# 1_Sheet_1_schdoc.net
KiCad netlist of a schematic drawn in Altium Designer
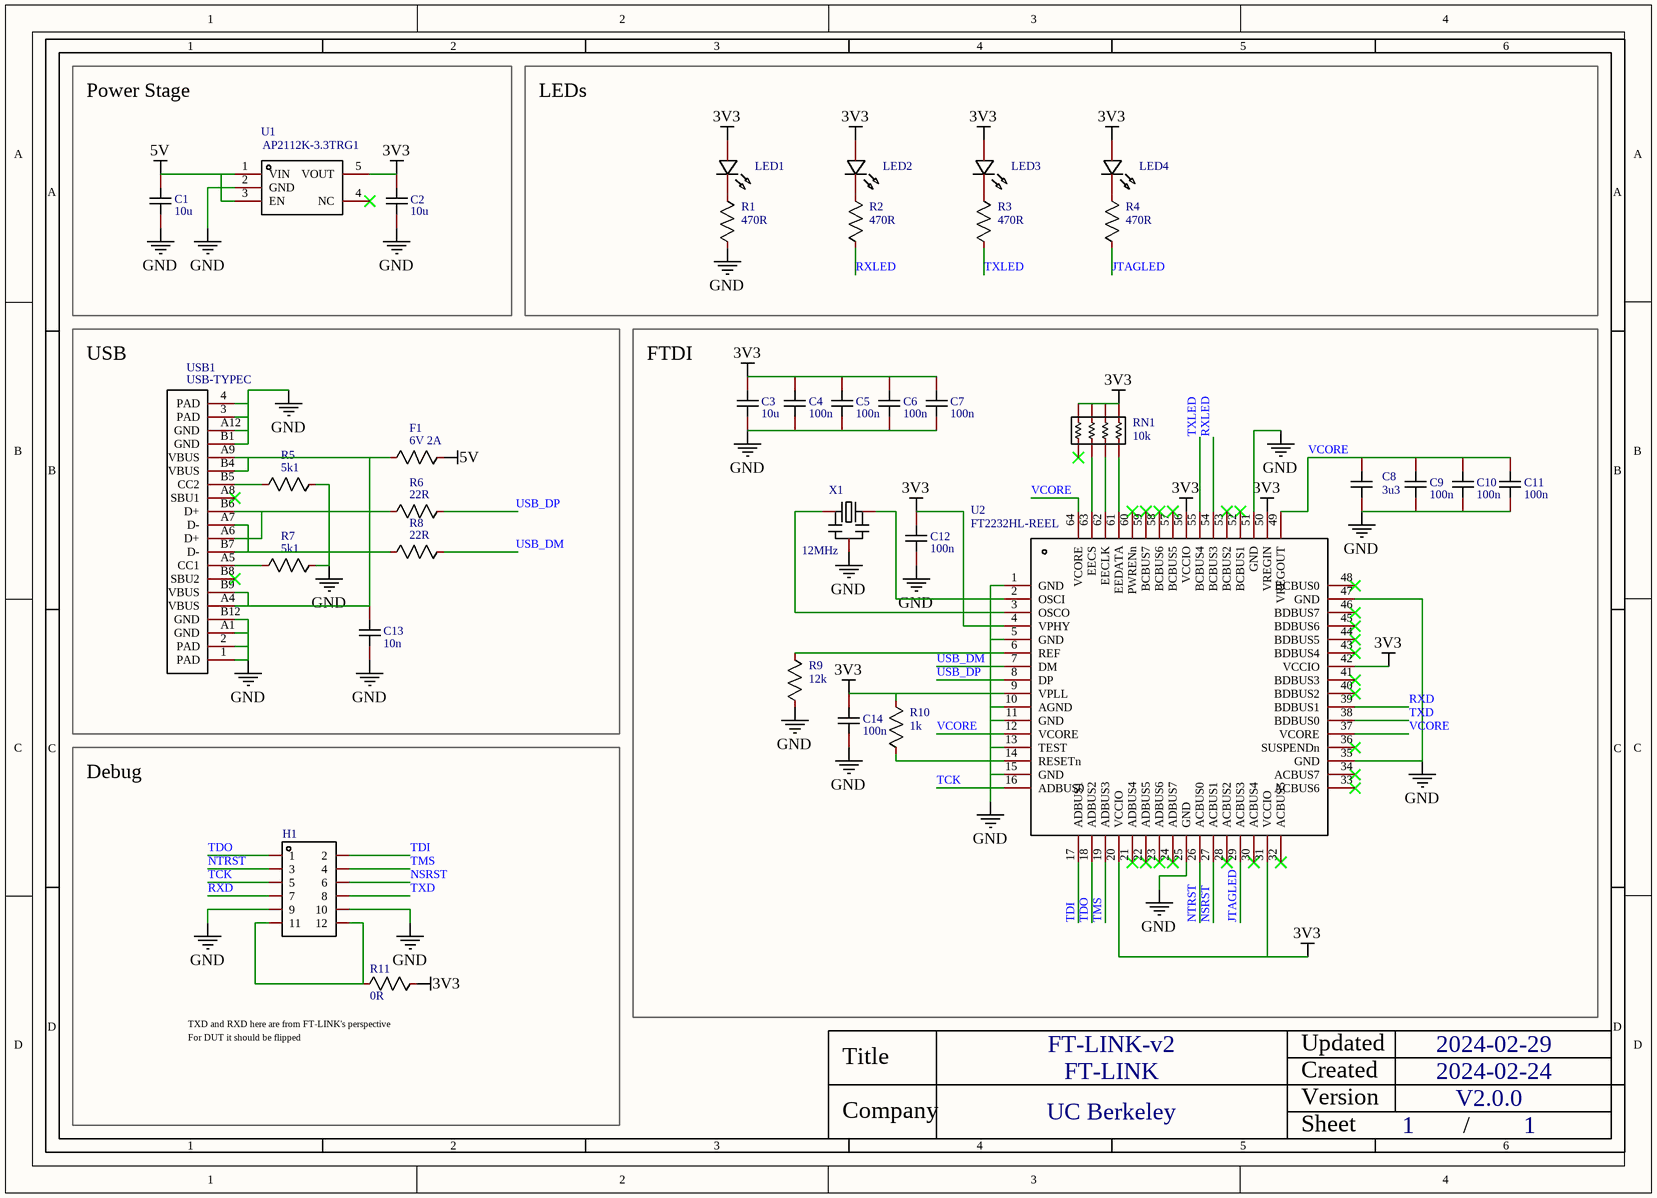
[diagram p0: 1_Sheet_1.schdoc.schdoc]

(export (version "E")
  (design (tool "Eeschema 10.0.6"))
  (components
    (comp (ref "C1")
      (value "10u")
      (fields
        (field (name "NAME") "10u")
        (field (name "MANUFACTURER PART") "CL10A106KP8NNNC")
        (field (name "MANUFACTURER") "SAMSUNG")
      )
      (libsource (lib "altium-import") (part "root_1_CL10A106KP8NNNC_"))
    )
    (comp (ref "C2")
      (value "10u")
      (fields
        (field (name "NAME") "10u")
        (field (name "MANUFACTURER PART") "CL10A106KP8NNNC")
        (field (name "MANUFACTURER") "SAMSUNG")
      )
      (libsource (lib "altium-import") (part "root_1_CL10A106KP8NNNC_"))
    )
    (comp (ref "C3")
      (value "10u")
      (fields
        (field (name "NAME") "10u")
        (field (name "MANUFACTURER PART") "CL10A106KP8NNNC")
        (field (name "MANUFACTURER") "SAMSUNG")
      )
      (libsource (lib "altium-import") (part "root_1_CL10A106KP8NNNC_"))
    )
    (comp (ref "C4")
      (value "100n")
      (fields
        (field (name "NAME") "100n")
        (field (name "MANUFACTURER PART") "CL05B104KB54PNC")
        (field (name "MANUFACTURER") "SAMSUNG")
      )
      (libsource (lib "altium-import") (part "root_1_CL05B104KB54PNC_"))
    )
    (comp (ref "C5")
      (value "100n")
      (fields
        (field (name "NAME") "100n")
        (field (name "MANUFACTURER PART") "CL05B104KB54PNC")
        (field (name "MANUFACTURER") "SAMSUNG")
      )
      (libsource (lib "altium-import") (part "root_1_CL05B104KB54PNC_"))
    )
    (comp (ref "C6")
      (value "100n")
      (fields
        (field (name "NAME") "100n")
        (field (name "MANUFACTURER PART") "CL05B104KB54PNC")
        (field (name "MANUFACTURER") "SAMSUNG")
      )
      (libsource (lib "altium-import") (part "root_1_CL05B104KB54PNC_"))
    )
    (comp (ref "C7")
      (value "100n")
      (fields
        (field (name "NAME") "100n")
        (field (name "MANUFACTURER PART") "CL05B104KB54PNC")
        (field (name "MANUFACTURER") "SAMSUNG")
      )
      (libsource (lib "altium-import") (part "root_1_CL05B104KB54PNC_"))
    )
    (comp (ref "C8")
      (value "3u3")
      (description "3.3uF ±10% 25V X5R")
      (fields
        (field (name "NAME") "3u3")
        (field (name "MANUFACTURER PART") "C1608X5R1E335KT000E")
        (field (name "MANUFACTURER") "TDK")
      )
      (libsource (lib "altium-import") (part "root_3_CAPA-0603_3u3_25V_"))
    )
    (comp (ref "C9")
      (value "100n")
      (fields
        (field (name "NAME") "100n")
        (field (name "MANUFACTURER PART") "CL05B104KB54PNC")
        (field (name "MANUFACTURER") "SAMSUNG")
      )
      (libsource (lib "altium-import") (part "root_1_CL05B104KB54PNC_"))
    )
    (comp (ref "C10")
      (value "100n")
      (fields
        (field (name "NAME") "100n")
        (field (name "MANUFACTURER PART") "CL05B104KB54PNC")
        (field (name "MANUFACTURER") "SAMSUNG")
      )
      (libsource (lib "altium-import") (part "root_1_CL05B104KB54PNC_"))
    )
    (comp (ref "C11")
      (value "100n")
      (fields
        (field (name "NAME") "100n")
        (field (name "MANUFACTURER PART") "CL05B104KB54PNC")
        (field (name "MANUFACTURER") "SAMSUNG")
      )
      (libsource (lib "altium-import") (part "root_1_CL05B104KB54PNC_"))
    )
    (comp (ref "C12")
      (value "100n")
      (fields
        (field (name "NAME") "100n")
        (field (name "MANUFACTURER PART") "CL05B104KB54PNC")
        (field (name "MANUFACTURER") "SAMSUNG")
      )
      (libsource (lib "altium-import") (part "root_1_CL05B104KB54PNC_"))
    )
    (comp (ref "C13")
      (value "10n")
      (fields
        (field (name "NAME") "10n")
        (field (name "MANUFACTURER PART") "CL05B103KB5NNNC")
        (field (name "MANUFACTURER") "SAMSUNG")
      )
      (libsource (lib "altium-import") (part "root_1_CL05B103KB5NNNC_"))
    )
    (comp (ref "C14")
      (value "100n")
      (fields
        (field (name "NAME") "100n")
        (field (name "MANUFACTURER PART") "CL05B104KB54PNC")
        (field (name "MANUFACTURER") "SAMSUNG")
      )
      (libsource (lib "altium-import") (part "root_1_CL05B104KB54PNC_"))
    )
    (comp (ref "F1")
      (value "6V 2A")
      (fields
        (field (name "NAME") "6V 2A")
        (field (name "MANUFACTURER PART") "SL0805200")
        (field (name "MANUFACTURER") "TECHFUSE")
      )
      (libsource (lib "altium-import") (part "root_0_SL0805200_"))
    )
    (comp (ref "H1")
      (value "A2541WR-2X6P")
      (fields (field (name "MANUFACTURER") "CJT 长江连接器") (field (name "MANUFACTURER PART") "A2541WR-2x6P"))
      (libsource (lib "altium-import") (part "root_0_A2541WR-2X6P_"))
    )
    (comp (ref "LED1")
      (value "LED-0603_R")
      (description "红灯 632nm")
      (fields
        (field (name "MANUFACTURER") "EVERLIGHT 台湾亿光")
        (field (name "MANUFACTURER PART") "19-217/R6C-AL1M2VY/3T")
      )
      (libsource (lib "altium-import") (part "root_3_LED-0603_R_"))
    )
    (comp (ref "LED2")
      (value "LED-0603_W")
      (description "白灯 高亮")
      (fields (field (name "MANUFACTURER") "KENTO") (field (name "MANUFACTURER PART") "LED White"))
      (libsource (lib "altium-import") (part "root_3_LED-0603_W_"))
    )
    (comp (ref "LED3")
      (value "LED-0603_W")
      (description "白灯 高亮")
      (fields (field (name "MANUFACTURER") "KENTO") (field (name "MANUFACTURER PART") "LED White"))
      (libsource (lib "altium-import") (part "root_3_LED-0603_W_"))
    )
    (comp (ref "LED4")
      (value "LED-0603_B")
      (description "蓝灯 高亮")
      (fields (field (name "MANUFACTURER") "KENTO") (field (name "MANUFACTURER PART") "XL-0603QBC"))
      (libsource (lib "altium-import") (part "root_3_LED-0603_B_"))
    )
    (comp (ref "R1")
      (value "470R")
      (description "厚膜电阻 470Ω ±1% 62.5mW")
      (fields
        (field (name "NAME") "470R")
        (field (name "MANUFACTURER PART") "0402WGF4700TCE")
        (field (name "MANUFACTURER") "UniOhm 台湾厚声")
      )
      (libsource (lib "altium-import") (part "root_1_RES-0402_470R_"))
    )
    (comp (ref "R2")
      (value "470R")
      (description "厚膜电阻 470Ω ±1% 62.5mW")
      (fields
        (field (name "NAME") "470R")
        (field (name "MANUFACTURER PART") "0402WGF4700TCE")
        (field (name "MANUFACTURER") "UniOhm 台湾厚声")
      )
      (libsource (lib "altium-import") (part "root_1_RES-0402_470R_"))
    )
    (comp (ref "R3")
      (value "470R")
      (description "厚膜电阻 470Ω ±1% 62.5mW")
      (fields
        (field (name "NAME") "470R")
        (field (name "MANUFACTURER PART") "0402WGF4700TCE")
        (field (name "MANUFACTURER") "UniOhm 台湾厚声")
      )
      (libsource (lib "altium-import") (part "root_1_RES-0402_470R_"))
    )
    (comp (ref "R4")
      (value "470R")
      (description "厚膜电阻 470Ω ±1% 62.5mW")
      (fields
        (field (name "NAME") "470R")
        (field (name "MANUFACTURER PART") "0402WGF4700TCE")
        (field (name "MANUFACTURER") "UniOhm 台湾厚声")
      )
      (libsource (lib "altium-import") (part "root_1_RES-0402_470R_"))
    )
    (comp (ref "R5")
      (value "5k1")
      (fields
        (field (name "NAME") "5k1")
        (field (name "MANUFACTURER PART") "0402WGF5101TCE")
        (field (name "MANUFACTURER") "UniOhm 台湾厚声")
      )
      (libsource (lib "altium-import") (part "root_0_0402WGF5101TCE_"))
    )
    (comp (ref "R6")
      (value "22R")
      (fields
        (field (name "NAME") "22R")
        (field (name "MANUFACTURER PART") "0402WGF220JTCE")
        (field (name "MANUFACTURER") "UniOhm 台湾厚声")
      )
      (libsource (lib "altium-import") (part "root_0_0402WGF220JTCE_"))
    )
    (comp (ref "R7")
      (value "5k1")
      (fields
        (field (name "NAME") "5k1")
        (field (name "MANUFACTURER PART") "0402WGF5101TCE")
        (field (name "MANUFACTURER") "UniOhm 台湾厚声")
      )
      (libsource (lib "altium-import") (part "root_0_0402WGF5101TCE_"))
    )
    (comp (ref "R8")
      (value "22R")
      (fields
        (field (name "NAME") "22R")
        (field (name "MANUFACTURER PART") "0402WGF220JTCE")
        (field (name "MANUFACTURER") "UniOhm 台湾厚声")
      )
      (libsource (lib "altium-import") (part "root_0_0402WGF220JTCE_"))
    )
    (comp (ref "R9")
      (value "12k")
      (description "厚膜电阻 12kΩ ±1% 62.5mW")
      (fields
        (field (name "NAME") "12k")
        (field (name "MANUFACTURER PART") "0402WGF1202TCE")
        (field (name "MANUFACTURER") "UniOhm 台湾厚声")
      )
      (libsource (lib "altium-import") (part "root_1_RES-0402_12k_"))
    )
    (comp (ref "R10")
      (value "1k")
      (description "厚膜电阻 1kΩ ±1% 62.5mW")
      (fields
        (field (name "NAME") "1k")
        (field (name "MANUFACTURER PART") "0402WGF1001TCE")
        (field (name "MANUFACTURER") "UniOhm 台湾厚声")
      )
      (libsource (lib "altium-import") (part "root_1_RES-0402_1k_"))
    )
    (comp (ref "R11")
      (value "0R")
      (fields (field (name "NAME") "0R"))
      (libsource (lib "altium-import") (part "root_0_RES-0402_TIE_"))
    )
    (comp (ref "RN1")
      (value "10k")
      (fields
        (field (name "NAME") "10k")
        (field (name "MANUFACTURER") "YAGEO 国巨")
        (field (name "MANUFACTURER PART") "YC124-FR-0710KL")
        (field (name "TOLERANCE") "±1%")
      )
      (libsource (lib "altium-import") (part "root_1_RES-0402x4_10k_"))
    )
    (comp (ref "U1")
      (value "AP2112K-3.3TRG1")
      (fields (field (name "NAME") "AP2112K-3.3TRG1") (field (name "MANUFACTURER") "DIODES"))
      (libsource (lib "altium-import") (part "root_0_AP2112K-3.3TRG1_"))
    )
    (comp (ref "U2")
      (value "FT2232HL-REEL")
      (description "应用功能:USB转UART；USB转FIFO;接口协议:UART;")
      (fields (field (name "NAME") "FT2232HL-REEL") (field (name "MANUFACTURER") "FTDI"))
      (libsource (lib "altium-import") (part "root_0_FT2232HL_"))
    )
    (comp (ref "USB1")
      (value "USB-TYPEC")
      (fields
        (field (name "NAME") "USB-TYPEC")
        (field (name "MANUFACTURER") "Shenzhen Kinghelm Elec")
        (field (name "MANUFACTURER PART") "KH-TYPE-C-16P")
      )
      (libsource (lib "altium-import") (part "root_2_KH-TYPE-C-16P_"))
    )
    (comp (ref "X1")
      (value "12MHz")
      (description "频率:12MHz;内置负载电容:33pF;谐振阻抗:30Ω;")
      (fields
        (field (name "NAME") "12MHz")
        (field (name "MANUFACTURER") "muRata 村田")
        (field (name "MANUFACTURER PART") "CSTNE12M0GH5C000R0")
      )
      (libsource (lib "altium-import") (part "root_0_CSTNE12M0GH5C000R0_"))
    )
  )
  (nets
    (net (code "1") (name "/JTAGLED") (class "Default")
      (node (ref "R4") (pin "1") (pinfunction "1_1") (pintype "passive"))
      (node (ref "U2") (pin "29") (pinfunction "ACBUS3_29") (pintype "passive"))
    )
    (net (code "2") (name "/NSRST") (class "Default")
      (node (ref "H1") (pin "6") (pinfunction "6_6") (pintype "passive"))
      (node (ref "U2") (pin "27") (pinfunction "ACBUS1_27") (pintype "passive"))
    )
    (net (code "3") (name "/NTRST") (class "Default")
      (node (ref "H1") (pin "3") (pinfunction "3_3") (pintype "passive"))
      (node (ref "U2") (pin "26") (pinfunction "ACBUS0_26") (pintype "passive"))
    )
    (net (code "4") (name "/RXD") (class "Default")
      (node (ref "H1") (pin "7") (pinfunction "7_7") (pintype "passive"))
      (node (ref "U2") (pin "39") (pinfunction "BDBUS1_39") (pintype "passive"))
    )
    (net (code "5") (name "/RXLED") (class "Default")
      (node (ref "R2") (pin "1") (pinfunction "1_1") (pintype "passive"))
      (node (ref "U2") (pin "54") (pinfunction "BCBUS3_54") (pintype "passive"))
    )
    (net (code "6") (name "/TCK") (class "Default")
      (node (ref "H1") (pin "5") (pinfunction "5_5") (pintype "passive"))
      (node (ref "U2") (pin "16") (pinfunction "ADBUS0_16") (pintype "passive"))
    )
    (net (code "7") (name "/TDI") (class "Default")
      (node (ref "H1") (pin "2") (pinfunction "2_2") (pintype "passive"))
      (node (ref "U2") (pin "17") (pinfunction "ADBUS1_17") (pintype "passive"))
    )
    (net (code "8") (name "/TDO") (class "Default")
      (node (ref "H1") (pin "1") (pinfunction "1_1") (pintype "passive"))
      (node (ref "U2") (pin "18") (pinfunction "ADBUS2_18") (pintype "passive"))
    )
    (net (code "9") (name "/TMS") (class "Default")
      (node (ref "H1") (pin "4") (pinfunction "4_4") (pintype "passive"))
      (node (ref "U2") (pin "19") (pinfunction "ADBUS3_19") (pintype "passive"))
    )
    (net (code "10") (name "/TXD") (class "Default")
      (node (ref "H1") (pin "8") (pinfunction "8_8") (pintype "passive"))
      (node (ref "U2") (pin "38") (pinfunction "BDBUS0_38") (pintype "passive"))
    )
    (net (code "11") (name "/TXLED") (class "Default")
      (node (ref "R3") (pin "1") (pinfunction "1_1") (pintype "passive"))
      (node (ref "U2") (pin "55") (pinfunction "BCBUS4_55") (pintype "passive"))
    )
    (net (code "12") (name "/USB_DM") (class "Default")
      (node (ref "R8") (pin "2") (pinfunction "2_2") (pintype "passive"))
      (node (ref "U2") (pin "7") (pinfunction "DM_7") (pintype "passive"))
    )
    (net (code "13") (name "/USB_DP") (class "Default")
      (node (ref "R6") (pin "2") (pinfunction "2_2") (pintype "passive"))
      (node (ref "U2") (pin "8") (pinfunction "DP_8") (pintype "passive"))
    )
    (net (code "14") (name "/VCORE") (class "Default")
      (node (ref "C10") (pin "2") (pinfunction "2_2") (pintype "passive"))
      (node (ref "C11") (pin "2") (pinfunction "2_2") (pintype "passive"))
      (node (ref "C8") (pin "1") (pinfunction "1_1") (pintype "passive"))
      (node (ref "C9") (pin "2") (pinfunction "2_2") (pintype "passive"))
      (node (ref "U2") (pin "12") (pinfunction "VCORE_12") (pintype "passive"))
      (node (ref "U2") (pin "37") (pinfunction "VCORE_37") (pintype "passive"))
      (node (ref "U2") (pin "49") (pinfunction "VREGOUT_49") (pintype "passive"))
      (node (ref "U2") (pin "64") (pinfunction "VCORE_64") (pintype "passive"))
    )
    (net (code "15") (name "3V3") (class "Default")
      (node (ref "C12") (pin "2") (pinfunction "2_2") (pintype "passive"))
      (node (ref "C14") (pin "2") (pinfunction "2_2") (pintype "passive"))
      (node (ref "C2") (pin "2") (pinfunction "2_2") (pintype "passive"))
      (node (ref "C3") (pin "2") (pinfunction "2_2") (pintype "passive"))
      (node (ref "C4") (pin "2") (pinfunction "2_2") (pintype "passive"))
      (node (ref "C5") (pin "2") (pinfunction "2_2") (pintype "passive"))
      (node (ref "C6") (pin "2") (pinfunction "2_2") (pintype "passive"))
      (node (ref "C7") (pin "2") (pinfunction "2_2") (pintype "passive"))
      (node (ref "LED1") (pin "2") (pinfunction "2_2") (pintype "passive"))
      (node (ref "LED2") (pin "2") (pinfunction "2_2") (pintype "passive"))
      (node (ref "LED3") (pin "2") (pinfunction "2_2") (pintype "passive"))
      (node (ref "LED4") (pin "2") (pinfunction "2_2") (pintype "passive"))
      (node (ref "R10") (pin "2") (pinfunction "2_2") (pintype "passive"))
      (node (ref "R11") (pin "2") (pinfunction "2_2") (pintype "passive"))
      (node (ref "RN1") (pin "5") (pinfunction "5_5") (pintype "passive"))
      (node (ref "RN1") (pin "6") (pinfunction "6_6") (pintype "passive"))
      (node (ref "RN1") (pin "7") (pinfunction "7_7") (pintype "passive"))
      (node (ref "RN1") (pin "8") (pinfunction "8_8") (pintype "passive"))
      (node (ref "U1") (pin "5") (pinfunction "VOUT_5") (pintype "passive"))
      (node (ref "U2") (pin "20") (pinfunction "VCCIO_20") (pintype "passive"))
      (node (ref "U2") (pin "31") (pinfunction "VCCIO_31") (pintype "passive"))
      (node (ref "U2") (pin "4") (pinfunction "VPHY_4") (pintype "passive"))
      (node (ref "U2") (pin "42") (pinfunction "VCCIO_42") (pintype "passive"))
      (node (ref "U2") (pin "50") (pinfunction "VREGIN_50") (pintype "passive"))
      (node (ref "U2") (pin "56") (pinfunction "VCCIO_56") (pintype "passive"))
      (node (ref "U2") (pin "9") (pinfunction "VPLL_9") (pintype "passive"))
    )
    (net (code "16") (name "5V") (class "Default")
      (node (ref "C1") (pin "2") (pinfunction "2_2") (pintype "passive"))
      (node (ref "F1") (pin "2") (pinfunction "2_2") (pintype "passive"))
      (node (ref "U1") (pin "1") (pinfunction "VIN_1") (pintype "passive"))
      (node (ref "U1") (pin "3") (pinfunction "EN_3") (pintype "passive"))
    )
    (net (code "17") (name "GND") (class "Default")
      (node (ref "C1") (pin "1") (pinfunction "1_1") (pintype "passive"))
      (node (ref "C10") (pin "1") (pinfunction "1_1") (pintype "passive"))
      (node (ref "C11") (pin "1") (pinfunction "1_1") (pintype "passive"))
      (node (ref "C12") (pin "1") (pinfunction "1_1") (pintype "passive"))
      (node (ref "C13") (pin "1") (pinfunction "1_1") (pintype "passive"))
      (node (ref "C14") (pin "1") (pinfunction "1_1") (pintype "passive"))
      (node (ref "C2") (pin "1") (pinfunction "1_1") (pintype "passive"))
      (node (ref "C3") (pin "1") (pinfunction "1_1") (pintype "passive"))
      (node (ref "C4") (pin "1") (pinfunction "1_1") (pintype "passive"))
      (node (ref "C5") (pin "1") (pinfunction "1_1") (pintype "passive"))
      (node (ref "C6") (pin "1") (pinfunction "1_1") (pintype "passive"))
      (node (ref "C7") (pin "1") (pinfunction "1_1") (pintype "passive"))
      (node (ref "C8") (pin "2") (pinfunction "2_2") (pintype "passive"))
      (node (ref "C9") (pin "1") (pinfunction "1_1") (pintype "passive"))
      (node (ref "H1") (pin "10") (pinfunction "10_10") (pintype "passive"))
      (node (ref "H1") (pin "9") (pinfunction "9_9") (pintype "passive"))
      (node (ref "R1") (pin "1") (pinfunction "1_1") (pintype "passive"))
      (node (ref "R5") (pin "2") (pinfunction "2_2") (pintype "passive"))
      (node (ref "R7") (pin "2") (pinfunction "2_2") (pintype "passive"))
      (node (ref "R9") (pin "1") (pinfunction "1_1") (pintype "passive"))
      (node (ref "U1") (pin "2") (pinfunction "GND_2") (pintype "passive"))
      (node (ref "U2") (pin "1") (pinfunction "GND_1") (pintype "passive"))
      (node (ref "U2") (pin "10") (pinfunction "AGND_10") (pintype "passive"))
      (node (ref "U2") (pin "11") (pinfunction "GND_11") (pintype "passive"))
      (node (ref "U2") (pin "13") (pinfunction "TEST_13") (pintype "passive"))
      (node (ref "U2") (pin "15") (pinfunction "GND_15") (pintype "passive"))
      (node (ref "U2") (pin "25") (pinfunction "GND_25") (pintype "passive"))
      (node (ref "U2") (pin "35") (pinfunction "GND_35") (pintype "passive"))
      (node (ref "U2") (pin "47") (pinfunction "GND_47") (pintype "passive"))
      (node (ref "U2") (pin "5") (pinfunction "GND_5") (pintype "passive"))
      (node (ref "U2") (pin "51") (pinfunction "GND_51") (pintype "passive"))
      (node (ref "USB1") (pin "1") (pinfunction "PAD_1") (pintype "passive"))
      (node (ref "USB1") (pin "2") (pinfunction "PAD_2") (pintype "passive"))
      (node (ref "USB1") (pin "3") (pinfunction "PAD_3") (pintype "passive"))
      (node (ref "USB1") (pin "4") (pinfunction "PAD_4") (pintype "passive"))
      (node (ref "USB1") (pin "A1") (pinfunction "GND_A1") (pintype "passive"))
      (node (ref "USB1") (pin "A12") (pinfunction "GND_A12") (pintype "passive"))
      (node (ref "USB1") (pin "B1") (pinfunction "GND_B1") (pintype "passive"))
      (node (ref "USB1") (pin "B12") (pinfunction "GND_B12") (pintype "passive"))
      (node (ref "X1") (pin "2") (pinfunction "GND_2") (pintype "passive"))
    )
    (net (code "18") (name "Net-(C13-Pad2)") (class "Default")
      (node (ref "C13") (pin "2") (pinfunction "2_2") (pintype "passive"))
      (node (ref "F1") (pin "1") (pinfunction "1_1") (pintype "passive"))
      (node (ref "USB1") (pin "A4") (pinfunction "VBUS_A4") (pintype "passive"))
      (node (ref "USB1") (pin "A9") (pinfunction "VBUS_A9") (pintype "passive"))
      (node (ref "USB1") (pin "B4") (pinfunction "VBUS_B4") (pintype "passive"))
      (node (ref "USB1") (pin "B9") (pinfunction "VBUS_B9") (pintype "passive"))
    )
    (net (code "19") (name "Net-(H1-Pad11)") (class "Default")
      (node (ref "H1") (pin "11") (pinfunction "11_11") (pintype "passive"))
      (node (ref "H1") (pin "12") (pinfunction "12_12") (pintype "passive"))
      (node (ref "R11") (pin "1") (pinfunction "1_1") (pintype "passive"))
    )
    (net (code "20") (name "Net-(LED1-Pad1)") (class "Default")
      (node (ref "LED1") (pin "1") (pinfunction "1_1") (pintype "passive"))
      (node (ref "R1") (pin "2") (pinfunction "2_2") (pintype "passive"))
    )
    (net (code "21") (name "Net-(LED2-Pad1)") (class "Default")
      (node (ref "LED2") (pin "1") (pinfunction "1_1") (pintype "passive"))
      (node (ref "R2") (pin "2") (pinfunction "2_2") (pintype "passive"))
    )
    (net (code "22") (name "Net-(LED3-Pad1)") (class "Default")
      (node (ref "LED3") (pin "1") (pinfunction "1_1") (pintype "passive"))
      (node (ref "R3") (pin "2") (pinfunction "2_2") (pintype "passive"))
    )
    (net (code "23") (name "Net-(LED4-Pad1)") (class "Default")
      (node (ref "LED4") (pin "1") (pinfunction "1_1") (pintype "passive"))
      (node (ref "R4") (pin "2") (pinfunction "2_2") (pintype "passive"))
    )
    (net (code "24") (name "Net-(R6-Pad1)") (class "Default")
      (node (ref "R6") (pin "1") (pinfunction "1_1") (pintype "passive"))
      (node (ref "USB1") (pin "A6") (pinfunction "D+_A6") (pintype "passive"))
      (node (ref "USB1") (pin "B6") (pinfunction "D+_B6") (pintype "passive"))
    )
    (net (code "25") (name "Net-(R8-Pad1)") (class "Default")
      (node (ref "R8") (pin "1") (pinfunction "1_1") (pintype "passive"))
      (node (ref "USB1") (pin "A7") (pinfunction "D-_A7") (pintype "passive"))
      (node (ref "USB1") (pin "B7") (pinfunction "D-_B7") (pintype "passive"))
    )
    (net (code "26") (name "Net-(U2-EECLK)") (class "Default")
      (node (ref "RN1") (pin "2") (pinfunction "2_2") (pintype "passive"))
      (node (ref "U2") (pin "62") (pinfunction "EECLK_62") (pintype "passive"))
    )
    (net (code "27") (name "Net-(U2-EECS)") (class "Default")
      (node (ref "RN1") (pin "3") (pinfunction "3_3") (pintype "passive"))
      (node (ref "U2") (pin "63") (pinfunction "EECS_63") (pintype "passive"))
    )
    (net (code "28") (name "Net-(U2-EEDATA)") (class "Default")
      (node (ref "RN1") (pin "1") (pinfunction "1_1") (pintype "passive"))
      (node (ref "U2") (pin "61") (pinfunction "EEDATA_61") (pintype "passive"))
    )
    (net (code "29") (name "Net-(U2-OSCI)") (class "Default")
      (node (ref "U2") (pin "2") (pinfunction "OSCI_2") (pintype "passive"))
      (node (ref "X1") (pin "3") (pinfunction "OUT_3") (pintype "passive"))
    )
    (net (code "30") (name "Net-(U2-OSCO)") (class "Default")
      (node (ref "U2") (pin "3") (pinfunction "OSCO_3") (pintype "passive"))
      (node (ref "X1") (pin "1") (pinfunction "IN_1") (pintype "passive"))
    )
    (net (code "31") (name "Net-(U2-REF)") (class "Default")
      (node (ref "R9") (pin "2") (pinfunction "2_2") (pintype "passive"))
      (node (ref "U2") (pin "6") (pinfunction "REF_6") (pintype "passive"))
    )
    (net (code "32") (name "Net-(U2-RESETn)") (class "Default")
      (node (ref "R10") (pin "1") (pinfunction "1_1") (pintype "passive"))
      (node (ref "U2") (pin "14") (pinfunction "RESETn_14") (pintype "passive"))
    )
    (net (code "33") (name "Net-(USB1-CC1)") (class "Default")
      (node (ref "R7") (pin "1") (pinfunction "1_1") (pintype "passive"))
      (node (ref "USB1") (pin "A5") (pinfunction "CC1_A5") (pintype "passive"))
    )
    (net (code "34") (name "Net-(USB1-CC2)") (class "Default")
      (node (ref "R5") (pin "1") (pinfunction "1_1") (pintype "passive"))
      (node (ref "USB1") (pin "B5") (pinfunction "CC2_B5") (pintype "passive"))
    )
    (net (code "35") (name "unconnected-(RN1-Pad4)") (class "Default")
      (node (ref "RN1") (pin "4") (pinfunction "4_4") (pintype "passive+no_connect"))
    )
    (net (code "36") (name "unconnected-(U1-NC-Pad4)") (class "Default")
      (node (ref "U1") (pin "4") (pinfunction "NC_4") (pintype "passive+no_connect"))
    )
    (net (code "37") (name "unconnected-(U2-ACBUS2-Pad28)") (class "Default")
      (node (ref "U2") (pin "28") (pinfunction "ACBUS2_28") (pintype "passive+no_connect"))
    )
    (net (code "38") (name "unconnected-(U2-ACBUS4-Pad30)") (class "Default")
      (node (ref "U2") (pin "30") (pinfunction "ACBUS4_30") (pintype "passive+no_connect"))
    )
    (net (code "39") (name "unconnected-(U2-ACBUS5-Pad32)") (class "Default")
      (node (ref "U2") (pin "32") (pinfunction "ACBUS5_32") (pintype "passive+no_connect"))
    )
    (net (code "40") (name "unconnected-(U2-ACBUS6-Pad33)") (class "Default")
      (node (ref "U2") (pin "33") (pinfunction "ACBUS6_33") (pintype "passive+no_connect"))
    )
    (net (code "41") (name "unconnected-(U2-ACBUS7-Pad34)") (class "Default")
      (node (ref "U2") (pin "34") (pinfunction "ACBUS7_34") (pintype "passive+no_connect"))
    )
    (net (code "42") (name "unconnected-(U2-ADBUS4-Pad21)") (class "Default")
      (node (ref "U2") (pin "21") (pinfunction "ADBUS4_21") (pintype "passive+no_connect"))
    )
    (net (code "43") (name "unconnected-(U2-ADBUS5-Pad22)") (class "Default")
      (node (ref "U2") (pin "22") (pinfunction "ADBUS5_22") (pintype "passive+no_connect"))
    )
    (net (code "44") (name "unconnected-(U2-ADBUS6-Pad23)") (class "Default")
      (node (ref "U2") (pin "23") (pinfunction "ADBUS6_23") (pintype "passive+no_connect"))
    )
    (net (code "45") (name "unconnected-(U2-ADBUS7-Pad24)") (class "Default")
      (node (ref "U2") (pin "24") (pinfunction "ADBUS7_24") (pintype "passive+no_connect"))
    )
    (net (code "46") (name "unconnected-(U2-BCBUS0-Pad48)") (class "Default")
      (node (ref "U2") (pin "48") (pinfunction "BCBUS0_48") (pintype "passive+no_connect"))
    )
    (net (code "47") (name "unconnected-(U2-BCBUS1-Pad52)") (class "Default")
      (node (ref "U2") (pin "52") (pinfunction "BCBUS1_52") (pintype "passive+no_connect"))
    )
    (net (code "48") (name "unconnected-(U2-BCBUS2-Pad53)") (class "Default")
      (node (ref "U2") (pin "53") (pinfunction "BCBUS2_53") (pintype "passive+no_connect"))
    )
    (net (code "49") (name "unconnected-(U2-BCBUS5-Pad57)") (class "Default")
      (node (ref "U2") (pin "57") (pinfunction "BCBUS5_57") (pintype "passive+no_connect"))
    )
    (net (code "50") (name "unconnected-(U2-BCBUS6-Pad58)") (class "Default")
      (node (ref "U2") (pin "58") (pinfunction "BCBUS6_58") (pintype "passive+no_connect"))
    )
    (net (code "51") (name "unconnected-(U2-BCBUS7-Pad59)") (class "Default")
      (node (ref "U2") (pin "59") (pinfunction "BCBUS7_59") (pintype "passive+no_connect"))
    )
    (net (code "52") (name "unconnected-(U2-BDBUS2-Pad40)") (class "Default")
      (node (ref "U2") (pin "40") (pinfunction "BDBUS2_40") (pintype "passive+no_connect"))
    )
    (net (code "53") (name "unconnected-(U2-BDBUS3-Pad41)") (class "Default")
      (node (ref "U2") (pin "41") (pinfunction "BDBUS3_41") (pintype "passive+no_connect"))
    )
    (net (code "54") (name "unconnected-(U2-BDBUS4-Pad43)") (class "Default")
      (node (ref "U2") (pin "43") (pinfunction "BDBUS4_43") (pintype "passive+no_connect"))
    )
    (net (code "55") (name "unconnected-(U2-BDBUS5-Pad44)") (class "Default")
      (node (ref "U2") (pin "44") (pinfunction "BDBUS5_44") (pintype "passive+no_connect"))
    )
    (net (code "56") (name "unconnected-(U2-BDBUS6-Pad45)") (class "Default")
      (node (ref "U2") (pin "45") (pinfunction "BDBUS6_45") (pintype "passive+no_connect"))
    )
    (net (code "57") (name "unconnected-(U2-BDBUS7-Pad46)") (class "Default")
      (node (ref "U2") (pin "46") (pinfunction "BDBUS7_46") (pintype "passive+no_connect"))
    )
    (net (code "58") (name "unconnected-(U2-PWRENn-Pad60)") (class "Default")
      (node (ref "U2") (pin "60") (pinfunction "PWRENn_60") (pintype "passive+no_connect"))
    )
    (net (code "59") (name "unconnected-(U2-SUSPENDn-Pad36)") (class "Default")
      (node (ref "U2") (pin "36") (pinfunction "SUSPENDn_36") (pintype "passive+no_connect"))
    )
    (net (code "60") (name "unconnected-(USB1-SBU1-PadA8)") (class "Default")
      (node (ref "USB1") (pin "A8") (pinfunction "SBU1_A8") (pintype "passive+no_connect"))
    )
    (net (code "61") (name "unconnected-(USB1-SBU2-PadB8)") (class "Default")
      (node (ref "USB1") (pin "B8") (pinfunction "SBU2_B8") (pintype "passive+no_connect"))
    )
  )
)
